# AIBoard.net
KiCad netlist of a schematic drawn in Altium Designer
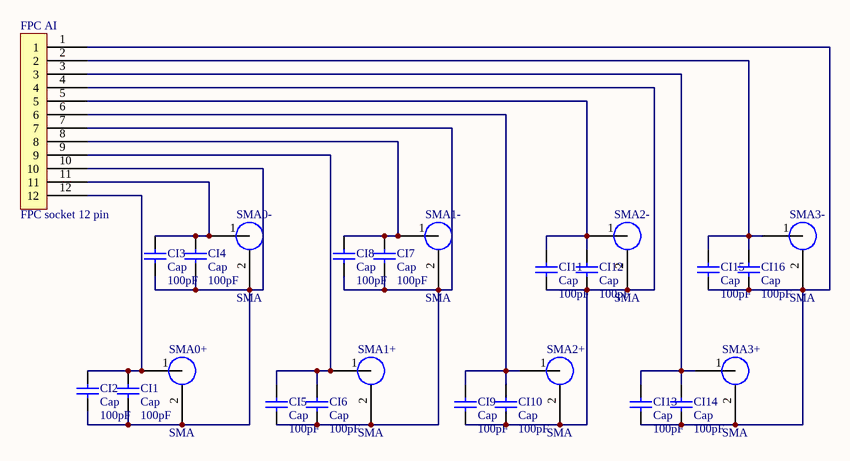
[diagram p0: AIBoard.SchDoc]

(export (version "E")
  (design (tool "Eeschema 10.0.6"))
  (components
    (comp (ref "CI1")
      (value "Cap")
      (footprint "RAD-0.3")
      (description "Capacitor")
      (fields (field (name "ALTIUM_VALUE") "100pF") (field (name "PUBLISHER") "Altium Limited"))
      (libsource (lib "Miscellaneous Devices") (part "Cap"))
    )
    (comp (ref "CI2")
      (value "Cap")
      (footprint "RAD-0.3")
      (description "Capacitor")
      (fields (field (name "ALTIUM_VALUE") "100pF") (field (name "PUBLISHER") "Altium Limited"))
      (libsource (lib "Miscellaneous Devices") (part "Cap"))
    )
    (comp (ref "CI3")
      (value "Cap")
      (footprint "RAD-0.3")
      (description "Capacitor")
      (fields (field (name "ALTIUM_VALUE") "100pF") (field (name "PUBLISHER") "Altium Limited"))
      (libsource (lib "Miscellaneous Devices") (part "Cap"))
    )
    (comp (ref "CI4")
      (value "Cap")
      (footprint "RAD-0.3")
      (description "Capacitor")
      (fields (field (name "ALTIUM_VALUE") "100pF") (field (name "PUBLISHER") "Altium Limited"))
      (libsource (lib "Miscellaneous Devices") (part "Cap"))
    )
    (comp (ref "CI5")
      (value "Cap")
      (footprint "RAD-0.3")
      (description "Capacitor")
      (fields (field (name "ALTIUM_VALUE") "100pF") (field (name "PUBLISHER") "Altium Limited"))
      (libsource (lib "Miscellaneous Devices") (part "Cap"))
    )
    (comp (ref "CI6")
      (value "Cap")
      (footprint "RAD-0.3")
      (description "Capacitor")
      (fields (field (name "ALTIUM_VALUE") "100pF") (field (name "PUBLISHER") "Altium Limited"))
      (libsource (lib "Miscellaneous Devices") (part "Cap"))
    )
    (comp (ref "CI7")
      (value "Cap")
      (footprint "RAD-0.3")
      (description "Capacitor")
      (fields (field (name "ALTIUM_VALUE") "100pF") (field (name "PUBLISHER") "Altium Limited"))
      (libsource (lib "Miscellaneous Devices") (part "Cap"))
    )
    (comp (ref "CI8")
      (value "Cap")
      (footprint "RAD-0.3")
      (description "Capacitor")
      (fields (field (name "ALTIUM_VALUE") "100pF") (field (name "PUBLISHER") "Altium Limited"))
      (libsource (lib "Miscellaneous Devices") (part "Cap"))
    )
    (comp (ref "CI9")
      (value "Cap")
      (footprint "RAD-0.3")
      (description "Capacitor")
      (fields (field (name "ALTIUM_VALUE") "100pF") (field (name "PUBLISHER") "Altium Limited"))
      (libsource (lib "Miscellaneous Devices") (part "Cap"))
    )
    (comp (ref "CI10")
      (value "Cap")
      (footprint "RAD-0.3")
      (description "Capacitor")
      (fields (field (name "ALTIUM_VALUE") "100pF") (field (name "PUBLISHER") "Altium Limited"))
      (libsource (lib "Miscellaneous Devices") (part "Cap"))
    )
    (comp (ref "CI11")
      (value "Cap")
      (footprint "RAD-0.3")
      (description "Capacitor")
      (fields (field (name "ALTIUM_VALUE") "100pF") (field (name "PUBLISHER") "Altium Limited"))
      (libsource (lib "Miscellaneous Devices") (part "Cap"))
    )
    (comp (ref "CI12")
      (value "Cap")
      (footprint "RAD-0.3")
      (description "Capacitor")
      (fields (field (name "ALTIUM_VALUE") "100pF") (field (name "PUBLISHER") "Altium Limited"))
      (libsource (lib "Miscellaneous Devices") (part "Cap"))
    )
    (comp (ref "CI13")
      (value "Cap")
      (footprint "RAD-0.3")
      (description "Capacitor")
      (fields (field (name "ALTIUM_VALUE") "100pF") (field (name "PUBLISHER") "Altium Limited"))
      (libsource (lib "Miscellaneous Devices") (part "Cap"))
    )
    (comp (ref "CI14")
      (value "Cap")
      (footprint "RAD-0.3")
      (description "Capacitor")
      (fields (field (name "ALTIUM_VALUE") "100pF") (field (name "PUBLISHER") "Altium Limited"))
      (libsource (lib "Miscellaneous Devices") (part "Cap"))
    )
    (comp (ref "CI15")
      (value "Cap")
      (footprint "RAD-0.3")
      (description "Capacitor")
      (fields (field (name "ALTIUM_VALUE") "100pF") (field (name "PUBLISHER") "Altium Limited"))
      (libsource (lib "Miscellaneous Devices") (part "Cap"))
    )
    (comp (ref "CI16")
      (value "Cap")
      (footprint "RAD-0.3")
      (description "Capacitor")
      (fields (field (name "ALTIUM_VALUE") "100pF") (field (name "PUBLISHER") "Altium Limited"))
      (libsource (lib "Miscellaneous Devices") (part "Cap"))
    )
    (comp (ref "FPC AI")
      (value "FPC socket 12 pin")
      (footprint "FPC 12pin")
      (libsource (lib "Libaray") (part "FPC socket 12 pin"))
    )
    (comp (ref "SMA0+") (value "SMA") (footprint "SMA") (libsource (lib "Libaray") (part "SMA")))
    (comp (ref "SMA0-") (value "SMA") (footprint "SMA") (libsource (lib "Libaray") (part "SMA")))
    (comp (ref "SMA1+") (value "SMA") (footprint "SMA") (libsource (lib "Libaray") (part "SMA")))
    (comp (ref "SMA1-") (value "SMA") (footprint "SMA") (libsource (lib "Libaray") (part "SMA")))
    (comp (ref "SMA2+") (value "SMA") (footprint "SMA") (libsource (lib "Libaray") (part "SMA")))
    (comp (ref "SMA2-") (value "SMA") (footprint "SMA") (libsource (lib "Libaray") (part "SMA")))
    (comp (ref "SMA3+") (value "SMA") (footprint "SMA") (libsource (lib "Libaray") (part "SMA")))
    (comp (ref "SMA3-") (value "SMA") (footprint "SMA") (libsource (lib "Libaray") (part "SMA")))
  )
  (nets
    (net (code "1") (name "Net-(SMA0+-Core)") (class "Default")
      (node (ref "CI1") (pin "2") (pinfunction "2_2") (pintype "passive"))
      (node (ref "CI2") (pin "2") (pinfunction "2_2") (pintype "passive"))
      (node (ref "FPC AI") (pin "12") (pinfunction "12_12") (pintype "passive"))
      (node (ref "SMA0+") (pin "1") (pinfunction "Core_1") (pintype "passive"))
    )
    (net (code "2") (name "Net-(SMA0+-Ground)") (class "Default")
      (node (ref "CI1") (pin "1") (pinfunction "1_1") (pintype "passive"))
      (node (ref "CI2") (pin "1") (pinfunction "1_1") (pintype "passive"))
      (node (ref "CI3") (pin "1") (pinfunction "1_1") (pintype "passive"))
      (node (ref "CI4") (pin "1") (pinfunction "1_1") (pintype "passive"))
      (node (ref "FPC AI") (pin "10") (pinfunction "10_10") (pintype "passive"))
      (node (ref "SMA0+") (pin "2") (pinfunction "Ground_2") (pintype "passive"))
      (node (ref "SMA0-") (pin "2") (pinfunction "Ground_2") (pintype "passive"))
    )
    (net (code "3") (name "Net-(SMA0--Core)") (class "Default")
      (node (ref "CI3") (pin "2") (pinfunction "2_2") (pintype "passive"))
      (node (ref "CI4") (pin "2") (pinfunction "2_2") (pintype "passive"))
      (node (ref "FPC AI") (pin "11") (pinfunction "11_11") (pintype "passive"))
      (node (ref "SMA0-") (pin "1") (pinfunction "Core_1") (pintype "passive"))
    )
    (net (code "4") (name "Net-(SMA1+-Core)") (class "Default")
      (node (ref "CI5") (pin "2") (pinfunction "2_2") (pintype "passive"))
      (node (ref "CI6") (pin "2") (pinfunction "2_2") (pintype "passive"))
      (node (ref "FPC AI") (pin "9") (pinfunction "9_9") (pintype "passive"))
      (node (ref "SMA1+") (pin "1") (pinfunction "Core_1") (pintype "passive"))
    )
    (net (code "5") (name "Net-(SMA1+-Ground)") (class "Default")
      (node (ref "CI5") (pin "1") (pinfunction "1_1") (pintype "passive"))
      (node (ref "CI6") (pin "1") (pinfunction "1_1") (pintype "passive"))
      (node (ref "CI7") (pin "1") (pinfunction "1_1") (pintype "passive"))
      (node (ref "CI8") (pin "1") (pinfunction "1_1") (pintype "passive"))
      (node (ref "FPC AI") (pin "7") (pinfunction "7_7") (pintype "passive"))
      (node (ref "SMA1+") (pin "2") (pinfunction "Ground_2") (pintype "passive"))
      (node (ref "SMA1-") (pin "2") (pinfunction "Ground_2") (pintype "passive"))
    )
    (net (code "6") (name "Net-(SMA1--Core)") (class "Default")
      (node (ref "CI7") (pin "2") (pinfunction "2_2") (pintype "passive"))
      (node (ref "CI8") (pin "2") (pinfunction "2_2") (pintype "passive"))
      (node (ref "FPC AI") (pin "8") (pinfunction "8_8") (pintype "passive"))
      (node (ref "SMA1-") (pin "1") (pinfunction "Core_1") (pintype "passive"))
    )
    (net (code "7") (name "Net-(SMA2+-Core)") (class "Default")
      (node (ref "CI10") (pin "2") (pinfunction "2_2") (pintype "passive"))
      (node (ref "CI9") (pin "2") (pinfunction "2_2") (pintype "passive"))
      (node (ref "FPC AI") (pin "6") (pinfunction "6_6") (pintype "passive"))
      (node (ref "SMA2+") (pin "1") (pinfunction "Core_1") (pintype "passive"))
    )
    (net (code "8") (name "Net-(SMA2+-Ground)") (class "Default")
      (node (ref "CI10") (pin "1") (pinfunction "1_1") (pintype "passive"))
      (node (ref "CI11") (pin "1") (pinfunction "1_1") (pintype "passive"))
      (node (ref "CI12") (pin "1") (pinfunction "1_1") (pintype "passive"))
      (node (ref "CI9") (pin "1") (pinfunction "1_1") (pintype "passive"))
      (node (ref "FPC AI") (pin "4") (pinfunction "4_4") (pintype "passive"))
      (node (ref "SMA2+") (pin "2") (pinfunction "Ground_2") (pintype "passive"))
      (node (ref "SMA2-") (pin "2") (pinfunction "Ground_2") (pintype "passive"))
    )
    (net (code "9") (name "Net-(SMA2--Core)") (class "Default")
      (node (ref "CI11") (pin "2") (pinfunction "2_2") (pintype "passive"))
      (node (ref "CI12") (pin "2") (pinfunction "2_2") (pintype "passive"))
      (node (ref "FPC AI") (pin "5") (pinfunction "5_5") (pintype "passive"))
      (node (ref "SMA2-") (pin "1") (pinfunction "Core_1") (pintype "passive"))
    )
    (net (code "10") (name "Net-(SMA3+-Core)") (class "Default")
      (node (ref "CI13") (pin "2") (pinfunction "2_2") (pintype "passive"))
      (node (ref "CI14") (pin "2") (pinfunction "2_2") (pintype "passive"))
      (node (ref "FPC AI") (pin "3") (pinfunction "3_3") (pintype "passive"))
      (node (ref "SMA3+") (pin "1") (pinfunction "Core_1") (pintype "passive"))
    )
    (net (code "11") (name "Net-(SMA3+-Ground)") (class "Default")
      (node (ref "CI13") (pin "1") (pinfunction "1_1") (pintype "passive"))
      (node (ref "CI14") (pin "1") (pinfunction "1_1") (pintype "passive"))
      (node (ref "CI15") (pin "1") (pinfunction "1_1") (pintype "passive"))
      (node (ref "CI16") (pin "1") (pinfunction "1_1") (pintype "passive"))
      (node (ref "FPC AI") (pin "1") (pinfunction "1_1") (pintype "passive"))
      (node (ref "SMA3+") (pin "2") (pinfunction "Ground_2") (pintype "passive"))
      (node (ref "SMA3-") (pin "2") (pinfunction "Ground_2") (pintype "passive"))
    )
    (net (code "12") (name "Net-(SMA3--Core)") (class "Default")
      (node (ref "CI15") (pin "2") (pinfunction "2_2") (pintype "passive"))
      (node (ref "CI16") (pin "2") (pinfunction "2_2") (pintype "passive"))
      (node (ref "FPC AI") (pin "2") (pinfunction "2_2") (pintype "passive"))
      (node (ref "SMA3-") (pin "1") (pinfunction "Core_1") (pintype "passive"))
    )
  )
)
